# board.net
KiCad netlist of a schematic drawn in EAGLE
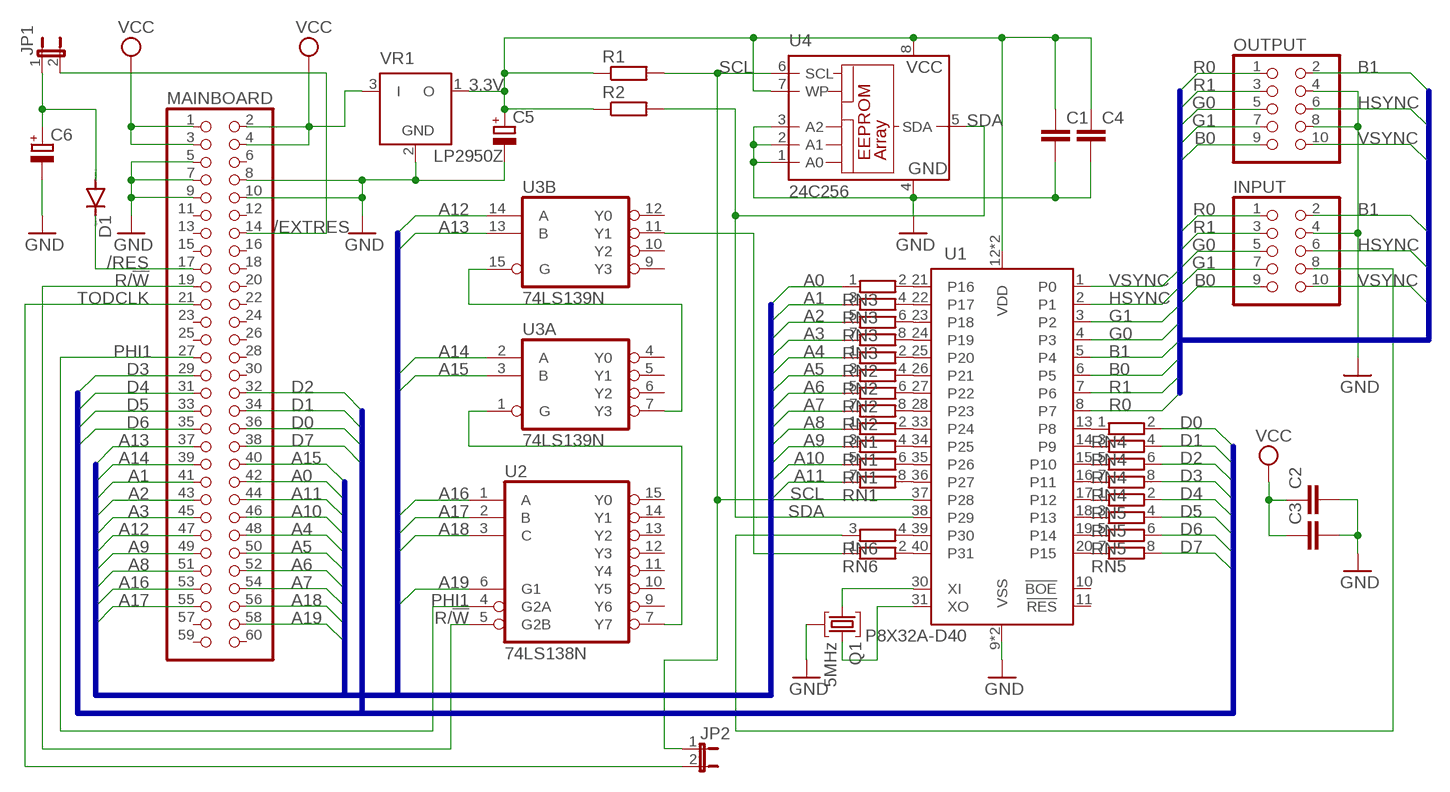
[diagram p0: schematic, sheet 1]

(export (version "E")
  (design (tool "Eeschema 10.0.6"))
  (components
    (comp (ref "C1")
      (value "C2.5/2")
      (footprint "eagle-import:C2.5-2")
      (libsource (lib "eagle-import") (part "C2.5/2"))
    )
    (comp (ref "C2")
      (value "C2.5/2")
      (footprint "eagle-import:C2.5-2")
      (libsource (lib "eagle-import") (part "C2.5/2"))
    )
    (comp (ref "C3")
      (value "C2.5/2")
      (footprint "eagle-import:C2.5-2")
      (libsource (lib "eagle-import") (part "C2.5/2"))
    )
    (comp (ref "C4")
      (value "C2.5/2")
      (footprint "eagle-import:C2.5-2")
      (libsource (lib "eagle-import") (part "C2.5/2"))
    )
    (comp (ref "C5")
      (value "CPOL-EUE5-6")
      (footprint "eagle-import:E5-6")
      (libsource (lib "eagle-import") (part "CPOL-EUE5-6"))
    )
    (comp (ref "C6")
      (value "CPOL-EUE5-6")
      (footprint "eagle-import:E5-6")
      (libsource (lib "eagle-import") (part "CPOL-EUE5-6"))
    )
    (comp (ref "D1")
      (value "1N4148DO35-7")
      (footprint "eagle-import:DO35-7")
      (libsource (lib "eagle-import") (part "1N4148DO35-7"))
    )
    (comp (ref "INPUT")
      (value "PINHD-2X5")
      (footprint "eagle-import:2X05")
      (libsource (lib "eagle-import") (part "PINHD-2X5"))
    )
    (comp (ref "JP1")
      (value "JP1E")
      (footprint "eagle-import:JP1")
      (libsource (lib "eagle-import") (part "JP1E"))
    )
    (comp (ref "JP2")
      (value "JP1E")
      (footprint "eagle-import:JP1")
      (libsource (lib "eagle-import") (part "JP1E"))
    )
    (comp (ref "MAINBOARD")
      (value "PINHD-2X30")
      (footprint "eagle-import:2X30")
      (libsource (lib "eagle-import") (part "PINHD-2X30"))
    )
    (comp (ref "OUTPUT")
      (value "PINHD-2X5")
      (footprint "eagle-import:2X05")
      (libsource (lib "eagle-import") (part "PINHD-2X5"))
    )
    (comp (ref "Q1")
      (value "5MHz")
      (footprint "eagle-import:UM1")
      (libsource (lib "eagle-import") (part "16M20AUM1"))
    )
    (comp (ref "R1")
      (value "R-EU_0204/7")
      (footprint "eagle-import:0204_7")
      (libsource (lib "eagle-import") (part "R-EU_0204/7"))
    )
    (comp (ref "R2")
      (value "R-EU_0204/7")
      (footprint "eagle-import:0204_7")
      (libsource (lib "eagle-import") (part "R-EU_0204/7"))
    )
    (comp (ref "RN1")
      (value "E4RP")
      (footprint "eagle-import:SIL8")
      (libsource (lib "eagle-import") (part "E4RP"))
    )
    (comp (ref "RN2")
      (value "E4RP")
      (footprint "eagle-import:SIL8")
      (libsource (lib "eagle-import") (part "E4RP"))
    )
    (comp (ref "RN3")
      (value "E4RP")
      (footprint "eagle-import:SIL8")
      (libsource (lib "eagle-import") (part "E4RP"))
    )
    (comp (ref "RN4")
      (value "E4RP")
      (footprint "eagle-import:SIL8")
      (libsource (lib "eagle-import") (part "E4RP"))
    )
    (comp (ref "RN5")
      (value "E4RP")
      (footprint "eagle-import:SIL8")
      (libsource (lib "eagle-import") (part "E4RP"))
    )
    (comp (ref "RN6")
      (value "E4RP")
      (footprint "eagle-import:SIL8")
      (libsource (lib "eagle-import") (part "E4RP"))
    )
    (comp (ref "U1")
      (value "P8X32A-D40")
      (footprint "eagle-import:DIL40")
      (fields (field (name "MF") "Parallax Semiconductor"))
      (libsource (lib "eagle-import") (part "P8X32A-?D40"))
    )
    (comp (ref "U2")
      (value "74LS138N")
      (footprint "eagle-import:DIL16")
      (libsource (lib "eagle-import") (part "74138NLS"))
    )
    (comp (ref "U3")
      (value "74LS139N")
      (footprint "eagle-import:DIL16")
      (libsource (lib "eagle-import") (part "74139NLS"))
    )
    (comp (ref "U4")
      (value "24C256")
      (footprint "eagle-import:DIL8")
      (fields (field (name "MF") "RAMTRON INTERNATIONAL CORP") (field (name "MPN") "FM24C64-P"))
      (libsource (lib "eagle-import") (part "24PC64"))
    )
    (comp (ref "VR1")
      (value "LP2950Z")
      (footprint "eagle-import:TO92")
      (libsource (lib "eagle-import") (part "LP2950Z"))
    )
  )
  (nets
    (net (code "1") (name "/3.3V") (class "Default")
      (node (ref "C1") (pin "1") (pinfunction "1_1") (pintype "passive"))
      (node (ref "C4") (pin "1") (pinfunction "1_1") (pintype "passive"))
      (node (ref "C5") (pin "+") (pinfunction "+_+") (pintype "passive"))
      (node (ref "R1") (pin "1") (pinfunction "1_1") (pintype "passive"))
      (node (ref "R2") (pin "1") (pinfunction "1_1") (pintype "passive"))
      (node (ref "U1") (pin "12") (pinfunction "VDD_12") (pintype "power_in"))
      (node (ref "U1") (pin "32") (pinfunction "VDD_32") (pintype "power_in"))
      (node (ref "U4") (pin "7") (pinfunction "WP_7") (pintype "input"))
      (node (ref "U4") (pin "8") (pinfunction "VCC_8") (pintype "power_in"))
      (node (ref "VR1") (pin "1") (pinfunction "O_1") (pintype "input"))
    )
    (net (code "2") (name "/A0") (class "Default")
      (node (ref "MAINBOARD") (pin "42") (pinfunction "42_42") (pintype "passive"))
      (node (ref "RN3") (pin "1") (pinfunction "1_1") (pintype "passive"))
    )
    (net (code "3") (name "/A1") (class "Default")
      (node (ref "MAINBOARD") (pin "41") (pinfunction "41_41") (pintype "passive"))
      (node (ref "RN3") (pin "3") (pinfunction "1_3") (pintype "passive"))
    )
    (net (code "4") (name "/A2") (class "Default")
      (node (ref "MAINBOARD") (pin "43") (pinfunction "43_43") (pintype "passive"))
      (node (ref "RN3") (pin "5") (pinfunction "1_5") (pintype "passive"))
    )
    (net (code "5") (name "/A3") (class "Default")
      (node (ref "MAINBOARD") (pin "45") (pinfunction "45_45") (pintype "passive"))
      (node (ref "RN3") (pin "7") (pinfunction "1_7") (pintype "passive"))
    )
    (net (code "6") (name "/A4") (class "Default")
      (node (ref "MAINBOARD") (pin "48") (pinfunction "48_48") (pintype "passive"))
      (node (ref "RN2") (pin "1") (pinfunction "1_1") (pintype "passive"))
    )
    (net (code "7") (name "/A5") (class "Default")
      (node (ref "MAINBOARD") (pin "50") (pinfunction "50_50") (pintype "passive"))
      (node (ref "RN2") (pin "3") (pinfunction "1_3") (pintype "passive"))
    )
    (net (code "8") (name "/A6") (class "Default")
      (node (ref "MAINBOARD") (pin "52") (pinfunction "52_52") (pintype "passive"))
      (node (ref "RN2") (pin "5") (pinfunction "1_5") (pintype "passive"))
    )
    (net (code "9") (name "/A7") (class "Default")
      (node (ref "MAINBOARD") (pin "54") (pinfunction "54_54") (pintype "passive"))
      (node (ref "RN2") (pin "7") (pinfunction "1_7") (pintype "passive"))
    )
    (net (code "10") (name "/A8") (class "Default")
      (node (ref "MAINBOARD") (pin "51") (pinfunction "51_51") (pintype "passive"))
      (node (ref "RN1") (pin "1") (pinfunction "1_1") (pintype "passive"))
    )
    (net (code "11") (name "/A9") (class "Default")
      (node (ref "MAINBOARD") (pin "49") (pinfunction "49_49") (pintype "passive"))
      (node (ref "RN1") (pin "3") (pinfunction "1_3") (pintype "passive"))
    )
    (net (code "12") (name "/A10") (class "Default")
      (node (ref "MAINBOARD") (pin "46") (pinfunction "46_46") (pintype "passive"))
      (node (ref "RN1") (pin "5") (pinfunction "1_5") (pintype "passive"))
    )
    (net (code "13") (name "/A11") (class "Default")
      (node (ref "MAINBOARD") (pin "44") (pinfunction "44_44") (pintype "passive"))
      (node (ref "RN1") (pin "7") (pinfunction "1_7") (pintype "passive"))
    )
    (net (code "14") (name "/A12") (class "Default")
      (node (ref "MAINBOARD") (pin "47") (pinfunction "47_47") (pintype "passive"))
      (node (ref "U3") (pin "14") (pinfunction "A_14") (pintype "input"))
    )
    (net (code "15") (name "/A13") (class "Default")
      (node (ref "MAINBOARD") (pin "37") (pinfunction "37_37") (pintype "passive"))
      (node (ref "U3") (pin "13") (pinfunction "B_13") (pintype "input"))
    )
    (net (code "16") (name "/A14") (class "Default")
      (node (ref "MAINBOARD") (pin "39") (pinfunction "39_39") (pintype "passive"))
      (node (ref "U3") (pin "2") (pinfunction "A_2") (pintype "input"))
    )
    (net (code "17") (name "/A15") (class "Default")
      (node (ref "MAINBOARD") (pin "40") (pinfunction "40_40") (pintype "passive"))
      (node (ref "U3") (pin "3") (pinfunction "B_3") (pintype "input"))
    )
    (net (code "18") (name "/A16") (class "Default")
      (node (ref "MAINBOARD") (pin "53") (pinfunction "53_53") (pintype "passive"))
      (node (ref "U2") (pin "1") (pinfunction "A_1") (pintype "input"))
    )
    (net (code "19") (name "/A17") (class "Default")
      (node (ref "MAINBOARD") (pin "55") (pinfunction "55_55") (pintype "passive"))
      (node (ref "U2") (pin "2") (pinfunction "B_2") (pintype "input"))
    )
    (net (code "20") (name "/A18") (class "Default")
      (node (ref "MAINBOARD") (pin "56") (pinfunction "56_56") (pintype "passive"))
      (node (ref "U2") (pin "3") (pinfunction "C_3") (pintype "input"))
    )
    (net (code "21") (name "/A19") (class "Default")
      (node (ref "MAINBOARD") (pin "58") (pinfunction "58_58") (pintype "passive"))
      (node (ref "U2") (pin "6") (pinfunction "G1_6") (pintype "input"))
    )
    (net (code "22") (name "/B0") (class "Default")
      (node (ref "INPUT") (pin "9") (pinfunction "9_9") (pintype "passive"))
      (node (ref "OUTPUT") (pin "9") (pinfunction "9_9") (pintype "passive"))
      (node (ref "U1") (pin "6") (pinfunction "P5_6") (pintype "bidirectional"))
    )
    (net (code "23") (name "/B1") (class "Default")
      (node (ref "INPUT") (pin "2") (pinfunction "2_2") (pintype "passive"))
      (node (ref "OUTPUT") (pin "2") (pinfunction "2_2") (pintype "passive"))
      (node (ref "U1") (pin "5") (pinfunction "P4_5") (pintype "bidirectional"))
    )
    (net (code "24") (name "/D0") (class "Default")
      (node (ref "MAINBOARD") (pin "36") (pinfunction "36_36") (pintype "passive"))
      (node (ref "RN4") (pin "2") (pinfunction "2_2") (pintype "passive"))
    )
    (net (code "25") (name "/D1") (class "Default")
      (node (ref "MAINBOARD") (pin "34") (pinfunction "34_34") (pintype "passive"))
      (node (ref "RN4") (pin "4") (pinfunction "2_4") (pintype "passive"))
    )
    (net (code "26") (name "/D2") (class "Default")
      (node (ref "MAINBOARD") (pin "32") (pinfunction "32_32") (pintype "passive"))
      (node (ref "RN4") (pin "6") (pinfunction "2_6") (pintype "passive"))
    )
    (net (code "27") (name "/D3") (class "Default")
      (node (ref "MAINBOARD") (pin "29") (pinfunction "29_29") (pintype "passive"))
      (node (ref "RN4") (pin "8") (pinfunction "2_8") (pintype "passive"))
    )
    (net (code "28") (name "/D4") (class "Default")
      (node (ref "MAINBOARD") (pin "31") (pinfunction "31_31") (pintype "passive"))
      (node (ref "RN5") (pin "2") (pinfunction "2_2") (pintype "passive"))
    )
    (net (code "29") (name "/D5") (class "Default")
      (node (ref "MAINBOARD") (pin "33") (pinfunction "33_33") (pintype "passive"))
      (node (ref "RN5") (pin "4") (pinfunction "2_4") (pintype "passive"))
    )
    (net (code "30") (name "/D6") (class "Default")
      (node (ref "MAINBOARD") (pin "35") (pinfunction "35_35") (pintype "passive"))
      (node (ref "RN5") (pin "6") (pinfunction "2_6") (pintype "passive"))
    )
    (net (code "31") (name "/D7") (class "Default")
      (node (ref "MAINBOARD") (pin "38") (pinfunction "38_38") (pintype "passive"))
      (node (ref "RN5") (pin "8") (pinfunction "2_8") (pintype "passive"))
    )
    (net (code "32") (name "/G0") (class "Default")
      (node (ref "INPUT") (pin "5") (pinfunction "5_5") (pintype "passive"))
      (node (ref "OUTPUT") (pin "5") (pinfunction "5_5") (pintype "passive"))
      (node (ref "U1") (pin "4") (pinfunction "P3_4") (pintype "bidirectional"))
    )
    (net (code "33") (name "/G1") (class "Default")
      (node (ref "INPUT") (pin "7") (pinfunction "7_7") (pintype "passive"))
      (node (ref "OUTPUT") (pin "7") (pinfunction "7_7") (pintype "passive"))
      (node (ref "U1") (pin "3") (pinfunction "P2_3") (pintype "bidirectional"))
    )
    (net (code "34") (name "/HSYNC") (class "Default")
      (node (ref "INPUT") (pin "6") (pinfunction "6_6") (pintype "passive"))
      (node (ref "OUTPUT") (pin "6") (pinfunction "6_6") (pintype "passive"))
      (node (ref "U1") (pin "2") (pinfunction "P1_2") (pintype "bidirectional"))
    )
    (net (code "35") (name "/PHI1") (class "Default")
      (node (ref "MAINBOARD") (pin "27") (pinfunction "27_27") (pintype "passive"))
      (node (ref "U2") (pin "4") (pinfunction "G2A_4") (pintype "input"))
    )
    (net (code "36") (name "/R0") (class "Default")
      (node (ref "INPUT") (pin "1") (pinfunction "1_1") (pintype "passive"))
      (node (ref "OUTPUT") (pin "1") (pinfunction "1_1") (pintype "passive"))
      (node (ref "U1") (pin "8") (pinfunction "P7_8") (pintype "bidirectional"))
    )
    (net (code "37") (name "/R1") (class "Default")
      (node (ref "INPUT") (pin "3") (pinfunction "3_3") (pintype "passive"))
      (node (ref "OUTPUT") (pin "3") (pinfunction "3_3") (pintype "passive"))
      (node (ref "U1") (pin "7") (pinfunction "P6_7") (pintype "bidirectional"))
    )
    (net (code "38") (name "/R{slash}~{W}") (class "Default")
      (node (ref "MAINBOARD") (pin "19") (pinfunction "19_19") (pintype "passive"))
      (node (ref "U2") (pin "5") (pinfunction "G2B_5") (pintype "input"))
    )
    (net (code "39") (name "/SCL") (class "Default")
      (node (ref "JP2") (pin "1") (pinfunction "1_1") (pintype "passive"))
      (node (ref "R1") (pin "2") (pinfunction "2_2") (pintype "passive"))
      (node (ref "U1") (pin "37") (pinfunction "P28_37") (pintype "bidirectional"))
      (node (ref "U4") (pin "6") (pinfunction "SCL_6") (pintype "input"))
    )
    (net (code "40") (name "/SDA") (class "Default")
      (node (ref "R2") (pin "2") (pinfunction "2_2") (pintype "passive"))
      (node (ref "U1") (pin "38") (pinfunction "P29_38") (pintype "bidirectional"))
      (node (ref "U4") (pin "5") (pinfunction "SDA_5") (pintype "bidirectional"))
    )
    (net (code "41") (name "/TODCLK") (class "Default")
      (node (ref "JP2") (pin "2") (pinfunction "2_2") (pintype "passive"))
      (node (ref "MAINBOARD") (pin "21") (pinfunction "21_21") (pintype "passive"))
    )
    (net (code "42") (name "/VSYNC") (class "Default")
      (node (ref "INPUT") (pin "10") (pinfunction "10_10") (pintype "passive"))
      (node (ref "OUTPUT") (pin "10") (pinfunction "10_10") (pintype "passive"))
      (node (ref "U1") (pin "1") (pinfunction "P0_1") (pintype "bidirectional"))
    )
    (net (code "43") (name "/{slash}EXTRES") (class "Default")
      (node (ref "JP1") (pin "2") (pinfunction "2_2") (pintype "passive"))
      (node (ref "MAINBOARD") (pin "14") (pinfunction "14_14") (pintype "passive"))
    )
    (net (code "44") (name "/{slash}RES") (class "Default")
      (node (ref "D1") (pin "C") (pinfunction "C_C") (pintype "passive"))
      (node (ref "MAINBOARD") (pin "17") (pinfunction "17_17") (pintype "passive"))
    )
    (net (code "45") (name "GND") (class "Default")
      (node (ref "C1") (pin "2") (pinfunction "2_2") (pintype "passive"))
      (node (ref "C2") (pin "2") (pinfunction "2_2") (pintype "passive"))
      (node (ref "C3") (pin "2") (pinfunction "2_2") (pintype "passive"))
      (node (ref "C4") (pin "2") (pinfunction "2_2") (pintype "passive"))
      (node (ref "C5") (pin "-") (pinfunction "-_-") (pintype "passive"))
      (node (ref "C6") (pin "-") (pinfunction "-_-") (pintype "passive"))
      (node (ref "INPUT") (pin "4") (pinfunction "4_4") (pintype "passive"))
      (node (ref "MAINBOARD") (pin "10") (pinfunction "10_10") (pintype "passive"))
      (node (ref "MAINBOARD") (pin "5") (pinfunction "5_5") (pintype "passive"))
      (node (ref "MAINBOARD") (pin "7") (pinfunction "7_7") (pintype "passive"))
      (node (ref "MAINBOARD") (pin "8") (pinfunction "8_8") (pintype "passive"))
      (node (ref "MAINBOARD") (pin "9") (pinfunction "9_9") (pintype "passive"))
      (node (ref "OUTPUT") (pin "4") (pinfunction "4_4") (pintype "passive"))
      (node (ref "OUTPUT") (pin "8") (pinfunction "8_8") (pintype "passive"))
      (node (ref "Q1") (pin "2") (pinfunction "2_2") (pintype "passive"))
      (node (ref "U1") (pin "29") (pinfunction "VSS_29") (pintype "power_in"))
      (node (ref "U1") (pin "9") (pinfunction "VSS_9") (pintype "power_in"))
      (node (ref "U4") (pin "1") (pinfunction "A0_1") (pintype "input"))
      (node (ref "U4") (pin "2") (pinfunction "A1_2") (pintype "input"))
      (node (ref "U4") (pin "3") (pinfunction "A2_3") (pintype "input"))
      (node (ref "U4") (pin "4") (pinfunction "GND_4") (pintype "power_in"))
      (node (ref "VR1") (pin "2") (pinfunction "GND_2") (pintype "power_in"))
    )
    (net (code "46") (name "Net-(C6-Pad+)") (class "Default")
      (node (ref "C6") (pin "+") (pinfunction "+_+") (pintype "passive"))
      (node (ref "D1") (pin "A") (pinfunction "A_A") (pintype "passive"))
      (node (ref "JP1") (pin "1") (pinfunction "1_1") (pintype "passive"))
    )
    (net (code "47") (name "Net-(RN1B-2)") (class "Default")
      (node (ref "RN1") (pin "4") (pinfunction "2_4") (pintype "passive"))
      (node (ref "U1") (pin "34") (pinfunction "P25_34") (pintype "bidirectional"))
    )
    (net (code "48") (name "Net-(RN1C-2)") (class "Default")
      (node (ref "RN1") (pin "6") (pinfunction "2_6") (pintype "passive"))
      (node (ref "U1") (pin "35") (pinfunction "P26_35") (pintype "bidirectional"))
    )
    (net (code "49") (name "Net-(RN1D-2)") (class "Default")
      (node (ref "RN1") (pin "8") (pinfunction "2_8") (pintype "passive"))
      (node (ref "U1") (pin "36") (pinfunction "P27_36") (pintype "bidirectional"))
    )
    (net (code "50") (name "Net-(RN2B-2)") (class "Default")
      (node (ref "RN2") (pin "4") (pinfunction "2_4") (pintype "passive"))
      (node (ref "U1") (pin "26") (pinfunction "P21_26") (pintype "bidirectional"))
    )
    (net (code "51") (name "Net-(RN2C-2)") (class "Default")
      (node (ref "RN2") (pin "6") (pinfunction "2_6") (pintype "passive"))
      (node (ref "U1") (pin "27") (pinfunction "P22_27") (pintype "bidirectional"))
    )
    (net (code "52") (name "Net-(RN2D-2)") (class "Default")
      (node (ref "RN2") (pin "8") (pinfunction "2_8") (pintype "passive"))
      (node (ref "U1") (pin "28") (pinfunction "P23_28") (pintype "bidirectional"))
    )
    (net (code "53") (name "Net-(RN3B-2)") (class "Default")
      (node (ref "RN3") (pin "4") (pinfunction "2_4") (pintype "passive"))
      (node (ref "U1") (pin "22") (pinfunction "P17_22") (pintype "bidirectional"))
    )
    (net (code "54") (name "Net-(RN3C-2)") (class "Default")
      (node (ref "RN3") (pin "6") (pinfunction "2_6") (pintype "passive"))
      (node (ref "U1") (pin "23") (pinfunction "P18_23") (pintype "bidirectional"))
    )
    (net (code "55") (name "Net-(RN3D-2)") (class "Default")
      (node (ref "RN3") (pin "8") (pinfunction "2_8") (pintype "passive"))
      (node (ref "U1") (pin "24") (pinfunction "P19_24") (pintype "bidirectional"))
    )
    (net (code "56") (name "Net-(RN4B-1)") (class "Default")
      (node (ref "RN4") (pin "3") (pinfunction "1_3") (pintype "passive"))
      (node (ref "U1") (pin "14") (pinfunction "P9_14") (pintype "bidirectional"))
    )
    (net (code "57") (name "Net-(RN4C-1)") (class "Default")
      (node (ref "RN4") (pin "5") (pinfunction "1_5") (pintype "passive"))
      (node (ref "U1") (pin "15") (pinfunction "P10_15") (pintype "bidirectional"))
    )
    (net (code "58") (name "Net-(RN4D-1)") (class "Default")
      (node (ref "RN4") (pin "7") (pinfunction "1_7") (pintype "passive"))
      (node (ref "U1") (pin "16") (pinfunction "P11_16") (pintype "bidirectional"))
    )
    (net (code "59") (name "Net-(RN5B-1)") (class "Default")
      (node (ref "RN5") (pin "3") (pinfunction "1_3") (pintype "passive"))
      (node (ref "U1") (pin "18") (pinfunction "P13_18") (pintype "bidirectional"))
    )
    (net (code "60") (name "Net-(RN5C-1)") (class "Default")
      (node (ref "RN5") (pin "5") (pinfunction "1_5") (pintype "passive"))
      (node (ref "U1") (pin "19") (pinfunction "P14_19") (pintype "bidirectional"))
    )
    (net (code "61") (name "Net-(RN5D-1)") (class "Default")
      (node (ref "RN5") (pin "7") (pinfunction "1_7") (pintype "passive"))
      (node (ref "U1") (pin "20") (pinfunction "P15_20") (pintype "bidirectional"))
    )
    (net (code "62") (name "Net-(RN6B-1)") (class "Default")
      (node (ref "INPUT") (pin "8") (pinfunction "8_8") (pintype "passive"))
      (node (ref "RN6") (pin "3") (pinfunction "1_3") (pintype "passive"))
    )
    (net (code "63") (name "Net-(RN6B-2)") (class "Default")
      (node (ref "RN6") (pin "4") (pinfunction "2_4") (pintype "passive"))
      (node (ref "U1") (pin "39") (pinfunction "P30_39") (pintype "bidirectional"))
    )
    (net (code "64") (name "Net-(U1-P8)") (class "Default")
      (node (ref "RN4") (pin "1") (pinfunction "1_1") (pintype "passive"))
      (node (ref "U1") (pin "13") (pinfunction "P8_13") (pintype "bidirectional"))
    )
    (net (code "65") (name "Net-(U1-P12)") (class "Default")
      (node (ref "RN5") (pin "1") (pinfunction "1_1") (pintype "passive"))
      (node (ref "U1") (pin "17") (pinfunction "P12_17") (pintype "bidirectional"))
    )
    (net (code "66") (name "Net-(U1-P16)") (class "Default")
      (node (ref "RN3") (pin "2") (pinfunction "2_2") (pintype "passive"))
      (node (ref "U1") (pin "21") (pinfunction "P16_21") (pintype "bidirectional"))
    )
    (net (code "67") (name "Net-(U1-P20)") (class "Default")
      (node (ref "RN2") (pin "2") (pinfunction "2_2") (pintype "passive"))
      (node (ref "U1") (pin "25") (pinfunction "P20_25") (pintype "bidirectional"))
    )
    (net (code "68") (name "Net-(U1-P24)") (class "Default")
      (node (ref "RN1") (pin "2") (pinfunction "2_2") (pintype "passive"))
      (node (ref "U1") (pin "33") (pinfunction "P24_33") (pintype "bidirectional"))
    )
    (net (code "69") (name "Net-(U1-P31)") (class "Default")
      (node (ref "RN6") (pin "2") (pinfunction "2_2") (pintype "passive"))
      (node (ref "U1") (pin "40") (pinfunction "P31_40") (pintype "bidirectional"))
    )
    (net (code "70") (name "Net-(U1-XI)") (class "Default")
      (node (ref "Q1") (pin "1") (pinfunction "1_1") (pintype "passive"))
      (node (ref "U1") (pin "30") (pinfunction "XI_30") (pintype "input"))
    )
    (net (code "71") (name "Net-(U1-XO)") (class "Default")
      (node (ref "Q1") (pin "3") (pinfunction "3_3") (pintype "passive"))
      (node (ref "U1") (pin "31") (pinfunction "XO_31") (pintype "output"))
    )
    (net (code "72") (name "Net-(U2A-Y7)") (class "Default")
      (node (ref "U2") (pin "7") (pinfunction "Y7_7") (pintype "output"))
      (node (ref "U3") (pin "1") (pinfunction "G_1") (pintype "input"))
    )
    (net (code "73") (name "Net-(U3A-Y3)") (class "Default")
      (node (ref "U3") (pin "15") (pinfunction "G_15") (pintype "input"))
      (node (ref "U3") (pin "7") (pinfunction "Y3_7") (pintype "output"))
    )
    (net (code "74") (name "Net-(U3B-Y1)") (class "Default")
      (node (ref "RN6") (pin "1") (pinfunction "1_1") (pintype "passive"))
      (node (ref "U3") (pin "11") (pinfunction "Y1_11") (pintype "output"))
    )
    (net (code "75") (name "VCC") (class "Default")
      (node (ref "C2") (pin "1") (pinfunction "1_1") (pintype "passive"))
      (node (ref "C3") (pin "1") (pinfunction "1_1") (pintype "passive"))
      (node (ref "MAINBOARD") (pin "1") (pinfunction "1_1") (pintype "passive"))
      (node (ref "MAINBOARD") (pin "2") (pinfunction "2_2") (pintype "passive"))
      (node (ref "MAINBOARD") (pin "3") (pinfunction "3_3") (pintype "passive"))
      (node (ref "MAINBOARD") (pin "4") (pinfunction "4_4") (pintype "passive"))
      (node (ref "VR1") (pin "3") (pinfunction "I_3") (pintype "input"))
    )
    (net (code "76") (name "unconnected-(MAINBOARD-Pad6)") (class "Default")
      (node (ref "MAINBOARD") (pin "6") (pinfunction "6_6") (pintype "passive"))
    )
    (net (code "77") (name "unconnected-(MAINBOARD-Pad11)") (class "Default")
      (node (ref "MAINBOARD") (pin "11") (pinfunction "11_11") (pintype "passive"))
    )
    (net (code "78") (name "unconnected-(MAINBOARD-Pad12)") (class "Default")
      (node (ref "MAINBOARD") (pin "12") (pinfunction "12_12") (pintype "passive"))
    )
    (net (code "79") (name "unconnected-(MAINBOARD-Pad13)") (class "Default")
      (node (ref "MAINBOARD") (pin "13") (pinfunction "13_13") (pintype "passive"))
    )
    (net (code "80") (name "unconnected-(MAINBOARD-Pad15)") (class "Default")
      (node (ref "MAINBOARD") (pin "15") (pinfunction "15_15") (pintype "passive"))
    )
    (net (code "81") (name "unconnected-(MAINBOARD-Pad16)") (class "Default")
      (node (ref "MAINBOARD") (pin "16") (pinfunction "16_16") (pintype "passive"))
    )
    (net (code "82") (name "unconnected-(MAINBOARD-Pad18)") (class "Default")
      (node (ref "MAINBOARD") (pin "18") (pinfunction "18_18") (pintype "passive"))
    )
    (net (code "83") (name "unconnected-(MAINBOARD-Pad20)") (class "Default")
      (node (ref "MAINBOARD") (pin "20") (pinfunction "20_20") (pintype "passive"))
    )
    (net (code "84") (name "unconnected-(MAINBOARD-Pad22)") (class "Default")
      (node (ref "MAINBOARD") (pin "22") (pinfunction "22_22") (pintype "passive"))
    )
    (net (code "85") (name "unconnected-(MAINBOARD-Pad23)") (class "Default")
      (node (ref "MAINBOARD") (pin "23") (pinfunction "23_23") (pintype "passive"))
    )
    (net (code "86") (name "unconnected-(MAINBOARD-Pad24)") (class "Default")
      (node (ref "MAINBOARD") (pin "24") (pinfunction "24_24") (pintype "passive"))
    )
    (net (code "87") (name "unconnected-(MAINBOARD-Pad25)") (class "Default")
      (node (ref "MAINBOARD") (pin "25") (pinfunction "25_25") (pintype "passive"))
    )
    (net (code "88") (name "unconnected-(MAINBOARD-Pad26)") (class "Default")
      (node (ref "MAINBOARD") (pin "26") (pinfunction "26_26") (pintype "passive"))
    )
    (net (code "89") (name "unconnected-(MAINBOARD-Pad28)") (class "Default")
      (node (ref "MAINBOARD") (pin "28") (pinfunction "28_28") (pintype "passive"))
    )
    (net (code "90") (name "unconnected-(MAINBOARD-Pad30)") (class "Default")
      (node (ref "MAINBOARD") (pin "30") (pinfunction "30_30") (pintype "passive"))
    )
    (net (code "91") (name "unconnected-(MAINBOARD-Pad57)") (class "Default")
      (node (ref "MAINBOARD") (pin "57") (pinfunction "57_57") (pintype "passive"))
    )
    (net (code "92") (name "unconnected-(MAINBOARD-Pad59)") (class "Default")
      (node (ref "MAINBOARD") (pin "59") (pinfunction "59_59") (pintype "passive"))
    )
    (net (code "93") (name "unconnected-(MAINBOARD-Pad60)") (class "Default")
      (node (ref "MAINBOARD") (pin "60") (pinfunction "60_60") (pintype "passive"))
    )
    (net (code "94") (name "unconnected-(U1-~{BOE}-Pad10)") (class "Default")
      (node (ref "U1") (pin "10") (pinfunction "~{BOE}_10") (pintype "input"))
    )
    (net (code "95") (name "unconnected-(U1-~{RES}-Pad11)") (class "Default")
      (node (ref "U1") (pin "11") (pinfunction "~{RES}_11") (pintype "passive"))
    )
    (net (code "96") (name "unconnected-(U2A-Y0-Pad15)") (class "Default")
      (node (ref "U2") (pin "15") (pinfunction "Y0_15") (pintype "output"))
    )
    (net (code "97") (name "unconnected-(U2A-Y1-Pad14)") (class "Default")
      (node (ref "U2") (pin "14") (pinfunction "Y1_14") (pintype "output"))
    )
    (net (code "98") (name "unconnected-(U2A-Y2-Pad13)") (class "Default")
      (node (ref "U2") (pin "13") (pinfunction "Y2_13") (pintype "output"))
    )
    (net (code "99") (name "unconnected-(U2A-Y3-Pad12)") (class "Default")
      (node (ref "U2") (pin "12") (pinfunction "Y3_12") (pintype "output"))
    )
    (net (code "100") (name "unconnected-(U2A-Y4-Pad11)") (class "Default")
      (node (ref "U2") (pin "11") (pinfunction "Y4_11") (pintype "output"))
    )
    (net (code "101") (name "unconnected-(U2A-Y5-Pad10)") (class "Default")
      (node (ref "U2") (pin "10") (pinfunction "Y5_10") (pintype "output"))
    )
    (net (code "102") (name "unconnected-(U2A-Y6-Pad9)") (class "Default")
      (node (ref "U2") (pin "9") (pinfunction "Y6_9") (pintype "output"))
    )
    (net (code "103") (name "unconnected-(U3A-Y0-Pad4)") (class "Default")
      (node (ref "U3") (pin "4") (pinfunction "Y0_4") (pintype "output"))
    )
    (net (code "104") (name "unconnected-(U3A-Y1-Pad5)") (class "Default")
      (node (ref "U3") (pin "5") (pinfunction "Y1_5") (pintype "output"))
    )
    (net (code "105") (name "unconnected-(U3A-Y2-Pad6)") (class "Default")
      (node (ref "U3") (pin "6") (pinfunction "Y2_6") (pintype "output"))
    )
    (net (code "106") (name "unconnected-(U3B-Y0-Pad12)") (class "Default")
      (node (ref "U3") (pin "12") (pinfunction "Y0_12") (pintype "output"))
    )
    (net (code "107") (name "unconnected-(U3B-Y2-Pad10)") (class "Default")
      (node (ref "U3") (pin "10") (pinfunction "Y2_10") (pintype "output"))
    )
    (net (code "108") (name "unconnected-(U3B-Y3-Pad9)") (class "Default")
      (node (ref "U3") (pin "9") (pinfunction "Y3_9") (pintype "output"))
    )
  )
)
